# Visualizacion_SCH.net
KiCad netlist of a schematic drawn in Altium Designer
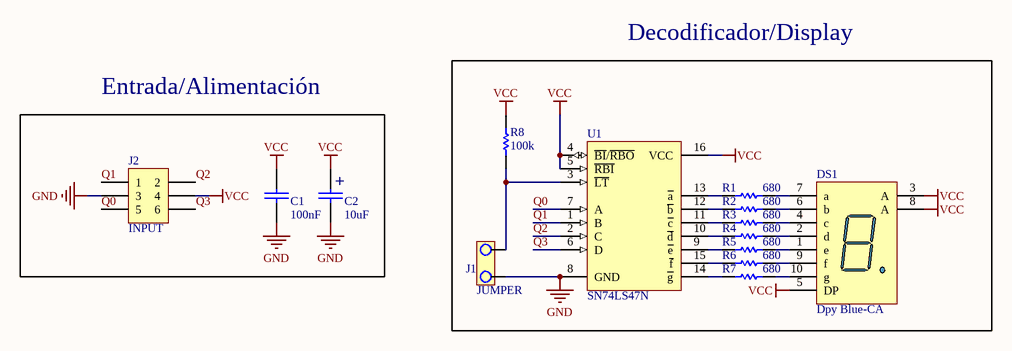
[diagram p0: Visualizacion_SCH.SchDoc]

(export (version "E")
  (design (tool "Eeschema 10.0.6"))
  (components
    (comp (ref "C1") (value "100nF") (footprint "0805") (libsource (lib "LIBEBAL") (part "CAP")))
    (comp (ref "C2") (value "10uF") (footprint "CAP100RP") (libsource (lib "LIBEBAL") (part "CAPPOL")))
    (comp (ref "DS1")
      (value "Dpy Blue-CA")
      (footprint "H")
      (description "14.2 mm General Purpose Blue 7-Segment Display: CA, RH DP, Gray Surface")
      (libsource (lib "Miscellaneous Devices") (part "Dpy Blue-CA"))
    )
    (comp (ref "J1") (value "JUMPER") (footprint "JUMPER2") (libsource (lib "LIBEBAL") (part "JUMPER")))
    (comp (ref "J2") (value "INPUT") (footprint "SIP3*2") (libsource (lib "LIBEBAL") (part "CON3*2")))
    (comp (ref "R1") (value "680") (footprint "0805") (libsource (lib "LIB PIO IX") (part "RES")))
    (comp (ref "R2") (value "680") (footprint "0805") (libsource (lib "LIB PIO IX") (part "RES")))
    (comp (ref "R3") (value "680") (footprint "0805") (libsource (lib "LIB PIO IX") (part "RES")))
    (comp (ref "R4") (value "680") (footprint "0805") (libsource (lib "LIB PIO IX") (part "RES")))
    (comp (ref "R5") (value "680") (footprint "0805") (libsource (lib "LIB PIO IX") (part "RES")))
    (comp (ref "R6") (value "680") (footprint "0805") (libsource (lib "LIB PIO IX") (part "RES")))
    (comp (ref "R7") (value "680") (footprint "0805") (libsource (lib "LIB PIO IX") (part "RES")))
    (comp (ref "R8") (value "100k") (footprint "0805") (libsource (lib "LIB PIO IX") (part "RES")))
    (comp (ref "U1")
      (value "SN74LS47N")
      (footprint "DIP16")
      (description "BCD-to-Seven-Segment Decoder/Driver")
      (libsource (lib "TI Interface Display Driver") (part "SN74LS47N"))
    )
  )
  (nets
    (net (code "1") (name "/Q0") (class "Default")
      (node (ref "J2") (pin "5") (pinfunction "5_5") (pintype "passive"))
      (node (ref "U1") (pin "7") (pinfunction "A_7") (pintype "input"))
    )
    (net (code "2") (name "/Q1") (class "Default")
      (node (ref "J2") (pin "1") (pinfunction "1_1") (pintype "passive"))
      (node (ref "U1") (pin "1") (pinfunction "B_1") (pintype "input"))
    )
    (net (code "3") (name "/Q2") (class "Default")
      (node (ref "J2") (pin "2") (pinfunction "2_2") (pintype "passive"))
      (node (ref "U1") (pin "2") (pinfunction "C_2") (pintype "input"))
    )
    (net (code "4") (name "/Q3") (class "Default")
      (node (ref "J2") (pin "6") (pinfunction "6_6") (pintype "passive"))
      (node (ref "U1") (pin "6") (pinfunction "D_6") (pintype "input"))
    )
    (net (code "5") (name "GND") (class "Default")
      (node (ref "C1") (pin "2") (pinfunction "2_2") (pintype "passive"))
      (node (ref "C2") (pin "2") (pinfunction "2_2") (pintype "passive"))
      (node (ref "J1") (pin "2") (pinfunction "2_2") (pintype "passive"))
      (node (ref "J2") (pin "3") (pinfunction "3_3") (pintype "passive"))
      (node (ref "U1") (pin "8") (pinfunction "GND_8") (pintype "power_in"))
    )
    (net (code "6") (name "Net-(DS1-a)") (class "Default")
      (node (ref "DS1") (pin "7") (pinfunction "a_7") (pintype "passive"))
      (node (ref "R1") (pin "2") (pinfunction "2_2") (pintype "passive"))
    )
    (net (code "7") (name "Net-(DS1-b)") (class "Default")
      (node (ref "DS1") (pin "6") (pinfunction "b_6") (pintype "passive"))
      (node (ref "R2") (pin "2") (pinfunction "2_2") (pintype "passive"))
    )
    (net (code "8") (name "Net-(DS1-c)") (class "Default")
      (node (ref "DS1") (pin "4") (pinfunction "c_4") (pintype "passive"))
      (node (ref "R3") (pin "2") (pinfunction "2_2") (pintype "passive"))
    )
    (net (code "9") (name "Net-(DS1-d)") (class "Default")
      (node (ref "DS1") (pin "2") (pinfunction "d_2") (pintype "passive"))
      (node (ref "R4") (pin "2") (pinfunction "2_2") (pintype "passive"))
    )
    (net (code "10") (name "Net-(DS1-e)") (class "Default")
      (node (ref "DS1") (pin "1") (pinfunction "e_1") (pintype "passive"))
      (node (ref "R5") (pin "2") (pinfunction "2_2") (pintype "passive"))
    )
    (net (code "11") (name "Net-(DS1-f)") (class "Default")
      (node (ref "DS1") (pin "9") (pinfunction "f_9") (pintype "passive"))
      (node (ref "R6") (pin "2") (pinfunction "2_2") (pintype "passive"))
    )
    (net (code "12") (name "Net-(DS1-g)") (class "Default")
      (node (ref "DS1") (pin "10") (pinfunction "g_10") (pintype "passive"))
      (node (ref "R7") (pin "2") (pinfunction "2_2") (pintype "passive"))
    )
    (net (code "13") (name "Net-(U1-~{LT})") (class "Default")
      (node (ref "J1") (pin "1") (pinfunction "1_1") (pintype "passive"))
      (node (ref "R8") (pin "1") (pinfunction "1_1") (pintype "passive"))
      (node (ref "U1") (pin "3") (pinfunction "~{LT}_3") (pintype "input"))
    )
    (net (code "14") (name "Net-(U1-~{a})") (class "Default")
      (node (ref "R1") (pin "1") (pinfunction "1_1") (pintype "passive"))
      (node (ref "U1") (pin "13") (pinfunction "~{a}_13") (pintype "open_collector"))
    )
    (net (code "15") (name "Net-(U1-~{b})") (class "Default")
      (node (ref "R2") (pin "1") (pinfunction "1_1") (pintype "passive"))
      (node (ref "U1") (pin "12") (pinfunction "~{b}_12") (pintype "open_collector"))
    )
    (net (code "16") (name "Net-(U1-~{c})") (class "Default")
      (node (ref "R3") (pin "1") (pinfunction "1_1") (pintype "passive"))
      (node (ref "U1") (pin "11") (pinfunction "~{c}_11") (pintype "open_collector"))
    )
    (net (code "17") (name "Net-(U1-~{d})") (class "Default")
      (node (ref "R4") (pin "1") (pinfunction "1_1") (pintype "passive"))
      (node (ref "U1") (pin "10") (pinfunction "~{d}_10") (pintype "open_collector"))
    )
    (net (code "18") (name "Net-(U1-~{e})") (class "Default")
      (node (ref "R5") (pin "1") (pinfunction "1_1") (pintype "passive"))
      (node (ref "U1") (pin "9") (pinfunction "~{e}_9") (pintype "open_collector"))
    )
    (net (code "19") (name "Net-(U1-~{f})") (class "Default")
      (node (ref "R6") (pin "1") (pinfunction "1_1") (pintype "passive"))
      (node (ref "U1") (pin "15") (pinfunction "~{f}_15") (pintype "open_collector"))
    )
    (net (code "20") (name "Net-(U1-~{g})") (class "Default")
      (node (ref "R7") (pin "1") (pinfunction "1_1") (pintype "passive"))
      (node (ref "U1") (pin "14") (pinfunction "~{g}_14") (pintype "open_collector"))
    )
    (net (code "21") (name "VCC") (class "Default")
      (node (ref "C1") (pin "1") (pinfunction "1_1") (pintype "passive"))
      (node (ref "C2") (pin "1") (pinfunction "1_1") (pintype "passive"))
      (node (ref "DS1") (pin "3") (pinfunction "A_3") (pintype "passive"))
      (node (ref "DS1") (pin "5") (pinfunction "DP_5") (pintype "passive"))
      (node (ref "DS1") (pin "8") (pinfunction "A_8") (pintype "passive"))
      (node (ref "J2") (pin "4") (pinfunction "4_4") (pintype "passive"))
      (node (ref "R8") (pin "2") (pinfunction "2_2") (pintype "passive"))
      (node (ref "U1") (pin "16") (pinfunction "VCC_16") (pintype "power_in"))
      (node (ref "U1") (pin "4") (pinfunction "~{BI}/~{RBO}_4") (pintype "bidirectional"))
      (node (ref "U1") (pin "5") (pinfunction "~{RBI}_5") (pintype "input"))
    )
  )
)
